# mcp23s17.net
KiCad netlist of a schematic drawn in EAGLE
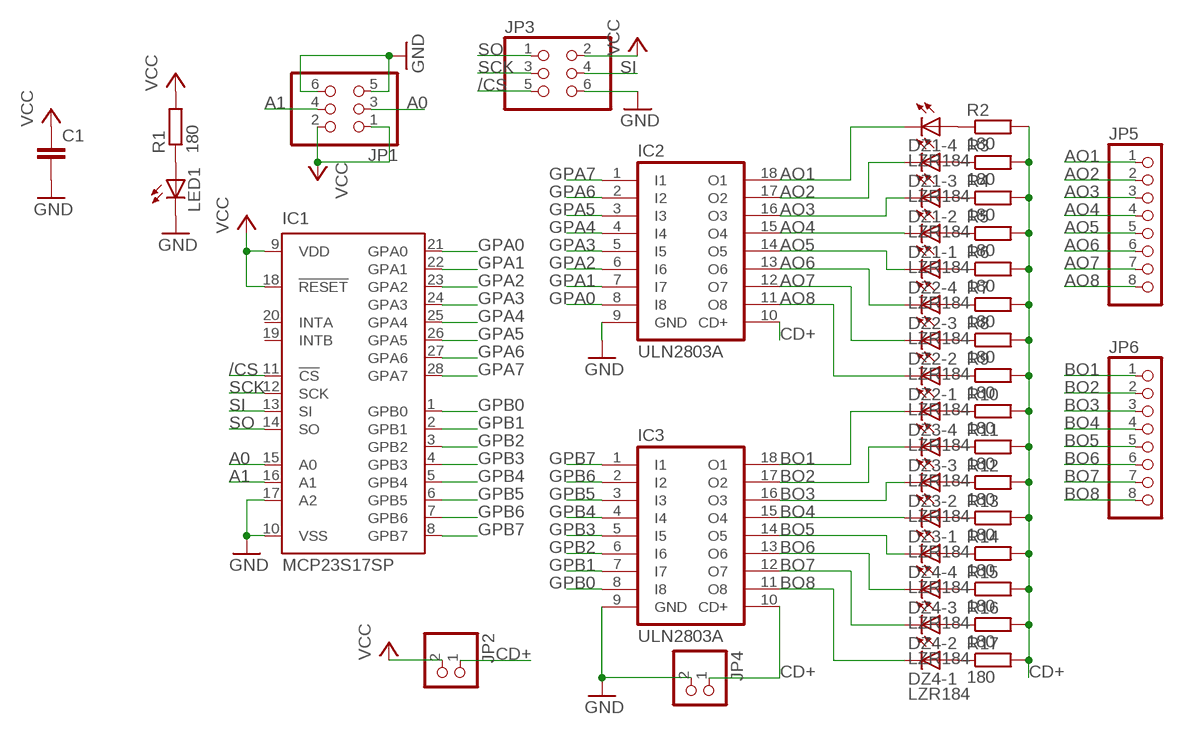
[diagram p0: schematic, sheet 1]

(export (version "E")
  (design (tool "Eeschema 10.0.6"))
  (components
    (comp (ref "C1")
      (value "C-EU050-024X044")
      (footprint "eagle-import:C050-024X044")
      (libsource (lib "eagle-import") (part "C-EU050-024X044"))
    )
    (comp (ref "DZ1")
      (value "LZR184")
      (footprint "eagle-import:LZR184")
      (libsource (lib "eagle-import") (part "LZR184"))
    )
    (comp (ref "DZ2")
      (value "LZR184")
      (footprint "eagle-import:LZR184")
      (libsource (lib "eagle-import") (part "LZR184"))
    )
    (comp (ref "DZ3")
      (value "LZR184")
      (footprint "eagle-import:LZR184")
      (libsource (lib "eagle-import") (part "LZR184"))
    )
    (comp (ref "DZ4")
      (value "LZR184")
      (footprint "eagle-import:LZR184")
      (libsource (lib "eagle-import") (part "LZR184"))
    )
    (comp (ref "IC1")
      (value "MCP23S17SP")
      (footprint "eagle-import:DIL28-3")
      (fields (field (name "MF") "MICROCHIP") (field (name "MPN") "MCP23S17-E/SP"))
      (libsource (lib "eagle-import") (part "MCP23S17SP"))
    )
    (comp (ref "IC2")
      (value "ULN2803A")
      (footprint "eagle-import:DIL18")
      (libsource (lib "eagle-import") (part "ULN2803A"))
    )
    (comp (ref "IC3")
      (value "ULN2803A")
      (footprint "eagle-import:DIL18")
      (libsource (lib "eagle-import") (part "ULN2803A"))
    )
    (comp (ref "JP1")
      (value "PINHD-2X3")
      (footprint "eagle-import:2X03")
      (libsource (lib "eagle-import") (part "PINHD-2X3"))
    )
    (comp (ref "JP2")
      (value "PINHD-1X2")
      (footprint "eagle-import:1X02")
      (libsource (lib "eagle-import") (part "PINHD-1X2"))
    )
    (comp (ref "JP3")
      (value "PINHD-2X3")
      (footprint "eagle-import:2X03")
      (libsource (lib "eagle-import") (part "PINHD-2X3"))
    )
    (comp (ref "JP4")
      (value "PINHD-1X2")
      (footprint "eagle-import:1X02")
      (libsource (lib "eagle-import") (part "PINHD-1X2"))
    )
    (comp (ref "JP5")
      (value "PINHD-1X8")
      (footprint "eagle-import:1X08")
      (libsource (lib "eagle-import") (part "PINHD-1X8"))
    )
    (comp (ref "JP6")
      (value "PINHD-1X8")
      (footprint "eagle-import:1X08")
      (libsource (lib "eagle-import") (part "PINHD-1X8"))
    )
    (comp (ref "LED1")
      (value "LED3MM")
      (footprint "eagle-import:LED3MM")
      (libsource (lib "eagle-import") (part "LED3MM"))
    )
    (comp (ref "R1")
      (value "180")
      (footprint "eagle-import:0204V")
      (libsource (lib "eagle-import") (part "R-EU_0204/2V"))
    )
    (comp (ref "R2")
      (value "180")
      (footprint "eagle-import:0204V")
      (libsource (lib "eagle-import") (part "R-EU_0204/2V"))
    )
    (comp (ref "R3")
      (value "180")
      (footprint "eagle-import:0204V")
      (libsource (lib "eagle-import") (part "R-EU_0204/2V"))
    )
    (comp (ref "R4")
      (value "180")
      (footprint "eagle-import:0204V")
      (libsource (lib "eagle-import") (part "R-EU_0204/2V"))
    )
    (comp (ref "R5")
      (value "180")
      (footprint "eagle-import:0204V")
      (libsource (lib "eagle-import") (part "R-EU_0204/2V"))
    )
    (comp (ref "R6")
      (value "180")
      (footprint "eagle-import:0204V")
      (libsource (lib "eagle-import") (part "R-EU_0204/2V"))
    )
    (comp (ref "R7")
      (value "180")
      (footprint "eagle-import:0204V")
      (libsource (lib "eagle-import") (part "R-EU_0204/2V"))
    )
    (comp (ref "R8")
      (value "180")
      (footprint "eagle-import:0204V")
      (libsource (lib "eagle-import") (part "R-EU_0204/2V"))
    )
    (comp (ref "R9")
      (value "180")
      (footprint "eagle-import:0204V")
      (libsource (lib "eagle-import") (part "R-EU_0204/2V"))
    )
    (comp (ref "R10")
      (value "180")
      (footprint "eagle-import:0204V")
      (libsource (lib "eagle-import") (part "R-EU_0204/2V"))
    )
    (comp (ref "R11")
      (value "180")
      (footprint "eagle-import:0204V")
      (libsource (lib "eagle-import") (part "R-EU_0204/2V"))
    )
    (comp (ref "R12")
      (value "180")
      (footprint "eagle-import:0204V")
      (libsource (lib "eagle-import") (part "R-EU_0204/2V"))
    )
    (comp (ref "R13")
      (value "180")
      (footprint "eagle-import:0204V")
      (libsource (lib "eagle-import") (part "R-EU_0204/2V"))
    )
    (comp (ref "R14")
      (value "180")
      (footprint "eagle-import:0204V")
      (libsource (lib "eagle-import") (part "R-EU_0204/2V"))
    )
    (comp (ref "R15")
      (value "180")
      (footprint "eagle-import:0204V")
      (libsource (lib "eagle-import") (part "R-EU_0204/2V"))
    )
    (comp (ref "R16")
      (value "180")
      (footprint "eagle-import:0204V")
      (libsource (lib "eagle-import") (part "R-EU_0204/2V"))
    )
    (comp (ref "R17")
      (value "180")
      (footprint "eagle-import:0204V")
      (libsource (lib "eagle-import") (part "R-EU_0204/2V"))
    )
  )
  (nets
    (net (code "1") (name "/A0") (class "Default")
      (node (ref "IC1") (pin "15") (pinfunction "A0_15") (pintype "input"))
      (node (ref "JP1") (pin "3") (pinfunction "3_3") (pintype "passive"))
    )
    (net (code "2") (name "/A1") (class "Default")
      (node (ref "IC1") (pin "16") (pinfunction "A1_16") (pintype "input"))
      (node (ref "JP1") (pin "4") (pinfunction "4_4") (pintype "passive"))
    )
    (net (code "3") (name "/AO1") (class "Default")
      (node (ref "DZ1") (pin "K4") (pinfunction "C_K4") (pintype "passive"))
      (node (ref "IC2") (pin "18") (pinfunction "O1_18") (pintype "open_collector"))
      (node (ref "JP5") (pin "1") (pinfunction "1_1") (pintype "passive"))
    )
    (net (code "4") (name "/AO2") (class "Default")
      (node (ref "DZ1") (pin "K3") (pinfunction "C_K3") (pintype "passive"))
      (node (ref "IC2") (pin "17") (pinfunction "O2_17") (pintype "open_collector"))
      (node (ref "JP5") (pin "2") (pinfunction "2_2") (pintype "passive"))
    )
    (net (code "5") (name "/AO3") (class "Default")
      (node (ref "DZ1") (pin "K2") (pinfunction "C_K2") (pintype "passive"))
      (node (ref "IC2") (pin "16") (pinfunction "O3_16") (pintype "open_collector"))
      (node (ref "JP5") (pin "3") (pinfunction "3_3") (pintype "passive"))
    )
    (net (code "6") (name "/AO4") (class "Default")
      (node (ref "DZ1") (pin "K1") (pinfunction "C_K1") (pintype "passive"))
      (node (ref "IC2") (pin "15") (pinfunction "O4_15") (pintype "open_collector"))
      (node (ref "JP5") (pin "4") (pinfunction "4_4") (pintype "passive"))
    )
    (net (code "7") (name "/AO5") (class "Default")
      (node (ref "DZ2") (pin "K4") (pinfunction "C_K4") (pintype "passive"))
      (node (ref "IC2") (pin "14") (pinfunction "O5_14") (pintype "open_collector"))
      (node (ref "JP5") (pin "5") (pinfunction "5_5") (pintype "passive"))
    )
    (net (code "8") (name "/AO6") (class "Default")
      (node (ref "DZ2") (pin "K3") (pinfunction "C_K3") (pintype "passive"))
      (node (ref "IC2") (pin "13") (pinfunction "O6_13") (pintype "open_collector"))
      (node (ref "JP5") (pin "6") (pinfunction "6_6") (pintype "passive"))
    )
    (net (code "9") (name "/AO7") (class "Default")
      (node (ref "DZ2") (pin "K2") (pinfunction "C_K2") (pintype "passive"))
      (node (ref "IC2") (pin "12") (pinfunction "O7_12") (pintype "open_collector"))
      (node (ref "JP5") (pin "7") (pinfunction "7_7") (pintype "passive"))
    )
    (net (code "10") (name "/AO8") (class "Default")
      (node (ref "DZ2") (pin "K1") (pinfunction "C_K1") (pintype "passive"))
      (node (ref "IC2") (pin "11") (pinfunction "O8_11") (pintype "open_collector"))
      (node (ref "JP5") (pin "8") (pinfunction "8_8") (pintype "passive"))
    )
    (net (code "11") (name "/BO1") (class "Default")
      (node (ref "DZ3") (pin "K4") (pinfunction "C_K4") (pintype "passive"))
      (node (ref "IC3") (pin "18") (pinfunction "O1_18") (pintype "open_collector"))
      (node (ref "JP6") (pin "1") (pinfunction "1_1") (pintype "passive"))
    )
    (net (code "12") (name "/BO2") (class "Default")
      (node (ref "DZ3") (pin "K3") (pinfunction "C_K3") (pintype "passive"))
      (node (ref "IC3") (pin "17") (pinfunction "O2_17") (pintype "open_collector"))
      (node (ref "JP6") (pin "2") (pinfunction "2_2") (pintype "passive"))
    )
    (net (code "13") (name "/BO3") (class "Default")
      (node (ref "DZ3") (pin "K2") (pinfunction "C_K2") (pintype "passive"))
      (node (ref "IC3") (pin "16") (pinfunction "O3_16") (pintype "open_collector"))
      (node (ref "JP6") (pin "3") (pinfunction "3_3") (pintype "passive"))
    )
    (net (code "14") (name "/BO4") (class "Default")
      (node (ref "DZ3") (pin "K1") (pinfunction "C_K1") (pintype "passive"))
      (node (ref "IC3") (pin "15") (pinfunction "O4_15") (pintype "open_collector"))
      (node (ref "JP6") (pin "4") (pinfunction "4_4") (pintype "passive"))
    )
    (net (code "15") (name "/BO5") (class "Default")
      (node (ref "DZ4") (pin "K4") (pinfunction "C_K4") (pintype "passive"))
      (node (ref "IC3") (pin "14") (pinfunction "O5_14") (pintype "open_collector"))
      (node (ref "JP6") (pin "5") (pinfunction "5_5") (pintype "passive"))
    )
    (net (code "16") (name "/BO6") (class "Default")
      (node (ref "DZ4") (pin "K3") (pinfunction "C_K3") (pintype "passive"))
      (node (ref "IC3") (pin "13") (pinfunction "O6_13") (pintype "open_collector"))
      (node (ref "JP6") (pin "6") (pinfunction "6_6") (pintype "passive"))
    )
    (net (code "17") (name "/BO7") (class "Default")
      (node (ref "DZ4") (pin "K2") (pinfunction "C_K2") (pintype "passive"))
      (node (ref "IC3") (pin "12") (pinfunction "O7_12") (pintype "open_collector"))
      (node (ref "JP6") (pin "7") (pinfunction "7_7") (pintype "passive"))
    )
    (net (code "18") (name "/BO8") (class "Default")
      (node (ref "DZ4") (pin "K1") (pinfunction "C_K1") (pintype "passive"))
      (node (ref "IC3") (pin "11") (pinfunction "O8_11") (pintype "open_collector"))
      (node (ref "JP6") (pin "8") (pinfunction "8_8") (pintype "passive"))
    )
    (net (code "19") (name "/CD+") (class "Default")
      (node (ref "IC2") (pin "10") (pinfunction "CD+_10") (pintype "passive"))
      (node (ref "IC3") (pin "10") (pinfunction "CD+_10") (pintype "passive"))
      (node (ref "JP2") (pin "1") (pinfunction "1_1") (pintype "passive"))
      (node (ref "JP4") (pin "1") (pinfunction "1_1") (pintype "passive"))
      (node (ref "R10") (pin "2") (pinfunction "2_2") (pintype "passive"))
      (node (ref "R11") (pin "2") (pinfunction "2_2") (pintype "passive"))
      (node (ref "R12") (pin "2") (pinfunction "2_2") (pintype "passive"))
      (node (ref "R13") (pin "2") (pinfunction "2_2") (pintype "passive"))
      (node (ref "R14") (pin "2") (pinfunction "2_2") (pintype "passive"))
      (node (ref "R15") (pin "2") (pinfunction "2_2") (pintype "passive"))
      (node (ref "R16") (pin "2") (pinfunction "2_2") (pintype "passive"))
      (node (ref "R17") (pin "2") (pinfunction "2_2") (pintype "passive"))
      (node (ref "R2") (pin "2") (pinfunction "2_2") (pintype "passive"))
      (node (ref "R3") (pin "2") (pinfunction "2_2") (pintype "passive"))
      (node (ref "R4") (pin "2") (pinfunction "2_2") (pintype "passive"))
      (node (ref "R5") (pin "2") (pinfunction "2_2") (pintype "passive"))
      (node (ref "R6") (pin "2") (pinfunction "2_2") (pintype "passive"))
      (node (ref "R7") (pin "2") (pinfunction "2_2") (pintype "passive"))
      (node (ref "R8") (pin "2") (pinfunction "2_2") (pintype "passive"))
      (node (ref "R9") (pin "2") (pinfunction "2_2") (pintype "passive"))
    )
    (net (code "20") (name "/GPA0") (class "Default")
      (node (ref "IC1") (pin "21") (pinfunction "GPA0_21") (pintype "bidirectional"))
      (node (ref "IC2") (pin "8") (pinfunction "I8_8") (pintype "input"))
    )
    (net (code "21") (name "/GPA1") (class "Default")
      (node (ref "IC1") (pin "22") (pinfunction "GPA1_22") (pintype "bidirectional"))
      (node (ref "IC2") (pin "7") (pinfunction "I7_7") (pintype "input"))
    )
    (net (code "22") (name "/GPA2") (class "Default")
      (node (ref "IC1") (pin "23") (pinfunction "GPA2_23") (pintype "bidirectional"))
      (node (ref "IC2") (pin "6") (pinfunction "I6_6") (pintype "input"))
    )
    (net (code "23") (name "/GPA3") (class "Default")
      (node (ref "IC1") (pin "24") (pinfunction "GPA3_24") (pintype "bidirectional"))
      (node (ref "IC2") (pin "5") (pinfunction "I5_5") (pintype "input"))
    )
    (net (code "24") (name "/GPA4") (class "Default")
      (node (ref "IC1") (pin "25") (pinfunction "GPA4_25") (pintype "bidirectional"))
      (node (ref "IC2") (pin "4") (pinfunction "I4_4") (pintype "input"))
    )
    (net (code "25") (name "/GPA5") (class "Default")
      (node (ref "IC1") (pin "26") (pinfunction "GPA5_26") (pintype "bidirectional"))
      (node (ref "IC2") (pin "3") (pinfunction "I3_3") (pintype "input"))
    )
    (net (code "26") (name "/GPA6") (class "Default")
      (node (ref "IC1") (pin "27") (pinfunction "GPA6_27") (pintype "bidirectional"))
      (node (ref "IC2") (pin "2") (pinfunction "I2_2") (pintype "input"))
    )
    (net (code "27") (name "/GPA7") (class "Default")
      (node (ref "IC1") (pin "28") (pinfunction "GPA7_28") (pintype "bidirectional"))
      (node (ref "IC2") (pin "1") (pinfunction "I1_1") (pintype "input"))
    )
    (net (code "28") (name "/GPB0") (class "Default")
      (node (ref "IC1") (pin "1") (pinfunction "GPB0_1") (pintype "bidirectional"))
      (node (ref "IC3") (pin "8") (pinfunction "I8_8") (pintype "input"))
    )
    (net (code "29") (name "/GPB1") (class "Default")
      (node (ref "IC1") (pin "2") (pinfunction "GPB1_2") (pintype "bidirectional"))
      (node (ref "IC3") (pin "7") (pinfunction "I7_7") (pintype "input"))
    )
    (net (code "30") (name "/GPB2") (class "Default")
      (node (ref "IC1") (pin "3") (pinfunction "GPB2_3") (pintype "bidirectional"))
      (node (ref "IC3") (pin "6") (pinfunction "I6_6") (pintype "input"))
    )
    (net (code "31") (name "/GPB3") (class "Default")
      (node (ref "IC1") (pin "4") (pinfunction "GPB3_4") (pintype "bidirectional"))
      (node (ref "IC3") (pin "5") (pinfunction "I5_5") (pintype "input"))
    )
    (net (code "32") (name "/GPB4") (class "Default")
      (node (ref "IC1") (pin "5") (pinfunction "GPB4_5") (pintype "bidirectional"))
      (node (ref "IC3") (pin "4") (pinfunction "I4_4") (pintype "input"))
    )
    (net (code "33") (name "/GPB5") (class "Default")
      (node (ref "IC1") (pin "6") (pinfunction "GPB5_6") (pintype "bidirectional"))
      (node (ref "IC3") (pin "3") (pinfunction "I3_3") (pintype "input"))
    )
    (net (code "34") (name "/GPB6") (class "Default")
      (node (ref "IC1") (pin "7") (pinfunction "GPB6_7") (pintype "bidirectional"))
      (node (ref "IC3") (pin "2") (pinfunction "I2_2") (pintype "input"))
    )
    (net (code "35") (name "/GPB7") (class "Default")
      (node (ref "IC1") (pin "8") (pinfunction "GPB7_8") (pintype "bidirectional"))
      (node (ref "IC3") (pin "1") (pinfunction "I1_1") (pintype "input"))
    )
    (net (code "36") (name "/SCK") (class "Default")
      (node (ref "IC1") (pin "12") (pinfunction "SCK_12") (pintype "input"))
      (node (ref "JP3") (pin "3") (pinfunction "3_3") (pintype "passive"))
    )
    (net (code "37") (name "/SI") (class "Default")
      (node (ref "IC1") (pin "13") (pinfunction "SI_13") (pintype "input"))
      (node (ref "JP3") (pin "4") (pinfunction "4_4") (pintype "passive"))
    )
    (net (code "38") (name "/SO") (class "Default")
      (node (ref "IC1") (pin "14") (pinfunction "SO_14") (pintype "output"))
      (node (ref "JP3") (pin "1") (pinfunction "1_1") (pintype "passive"))
    )
    (net (code "39") (name "/{slash}CS") (class "Default")
      (node (ref "IC1") (pin "11") (pinfunction "~{CS}_11") (pintype "input"))
      (node (ref "JP3") (pin "5") (pinfunction "5_5") (pintype "passive"))
    )
    (net (code "40") (name "GND") (class "Default")
      (node (ref "C1") (pin "2") (pinfunction "2_2") (pintype "passive"))
      (node (ref "IC1") (pin "10") (pinfunction "VSS_10") (pintype "power_in"))
      (node (ref "IC1") (pin "17") (pinfunction "A2_17") (pintype "input"))
      (node (ref "IC2") (pin "9") (pinfunction "GND_9") (pintype "power_in"))
      (node (ref "IC3") (pin "9") (pinfunction "GND_9") (pintype "power_in"))
      (node (ref "JP1") (pin "5") (pinfunction "5_5") (pintype "passive"))
      (node (ref "JP1") (pin "6") (pinfunction "6_6") (pintype "passive"))
      (node (ref "JP3") (pin "6") (pinfunction "6_6") (pintype "passive"))
      (node (ref "JP4") (pin "2") (pinfunction "2_2") (pintype "passive"))
      (node (ref "LED1") (pin "K") (pinfunction "C_K") (pintype "passive"))
    )
    (net (code "41") (name "Net-(DZ1A-A)") (class "Default")
      (node (ref "DZ1") (pin "A1") (pinfunction "A_A1") (pintype "passive"))
      (node (ref "R5") (pin "1") (pinfunction "1_1") (pintype "passive"))
    )
    (net (code "42") (name "Net-(DZ1B-A)") (class "Default")
      (node (ref "DZ1") (pin "A2") (pinfunction "A_A2") (pintype "passive"))
      (node (ref "R4") (pin "1") (pinfunction "1_1") (pintype "passive"))
    )
    (net (code "43") (name "Net-(DZ1C-A)") (class "Default")
      (node (ref "DZ1") (pin "A3") (pinfunction "A_A3") (pintype "passive"))
      (node (ref "R3") (pin "1") (pinfunction "1_1") (pintype "passive"))
    )
    (net (code "44") (name "Net-(DZ1D-A)") (class "Default")
      (node (ref "DZ1") (pin "A4") (pinfunction "A_A4") (pintype "passive"))
      (node (ref "R2") (pin "1") (pinfunction "1_1") (pintype "passive"))
    )
    (net (code "45") (name "Net-(DZ2A-A)") (class "Default")
      (node (ref "DZ2") (pin "A1") (pinfunction "A_A1") (pintype "passive"))
      (node (ref "R9") (pin "1") (pinfunction "1_1") (pintype "passive"))
    )
    (net (code "46") (name "Net-(DZ2B-A)") (class "Default")
      (node (ref "DZ2") (pin "A2") (pinfunction "A_A2") (pintype "passive"))
      (node (ref "R8") (pin "1") (pinfunction "1_1") (pintype "passive"))
    )
    (net (code "47") (name "Net-(DZ2C-A)") (class "Default")
      (node (ref "DZ2") (pin "A3") (pinfunction "A_A3") (pintype "passive"))
      (node (ref "R7") (pin "1") (pinfunction "1_1") (pintype "passive"))
    )
    (net (code "48") (name "Net-(DZ2D-A)") (class "Default")
      (node (ref "DZ2") (pin "A4") (pinfunction "A_A4") (pintype "passive"))
      (node (ref "R6") (pin "1") (pinfunction "1_1") (pintype "passive"))
    )
    (net (code "49") (name "Net-(DZ3A-A)") (class "Default")
      (node (ref "DZ3") (pin "A1") (pinfunction "A_A1") (pintype "passive"))
      (node (ref "R13") (pin "1") (pinfunction "1_1") (pintype "passive"))
    )
    (net (code "50") (name "Net-(DZ3B-A)") (class "Default")
      (node (ref "DZ3") (pin "A2") (pinfunction "A_A2") (pintype "passive"))
      (node (ref "R12") (pin "1") (pinfunction "1_1") (pintype "passive"))
    )
    (net (code "51") (name "Net-(DZ3C-A)") (class "Default")
      (node (ref "DZ3") (pin "A3") (pinfunction "A_A3") (pintype "passive"))
      (node (ref "R11") (pin "1") (pinfunction "1_1") (pintype "passive"))
    )
    (net (code "52") (name "Net-(DZ3D-A)") (class "Default")
      (node (ref "DZ3") (pin "A4") (pinfunction "A_A4") (pintype "passive"))
      (node (ref "R10") (pin "1") (pinfunction "1_1") (pintype "passive"))
    )
    (net (code "53") (name "Net-(DZ4A-A)") (class "Default")
      (node (ref "DZ4") (pin "A1") (pinfunction "A_A1") (pintype "passive"))
      (node (ref "R17") (pin "1") (pinfunction "1_1") (pintype "passive"))
    )
    (net (code "54") (name "Net-(DZ4B-A)") (class "Default")
      (node (ref "DZ4") (pin "A2") (pinfunction "A_A2") (pintype "passive"))
      (node (ref "R16") (pin "1") (pinfunction "1_1") (pintype "passive"))
    )
    (net (code "55") (name "Net-(DZ4C-A)") (class "Default")
      (node (ref "DZ4") (pin "A3") (pinfunction "A_A3") (pintype "passive"))
      (node (ref "R15") (pin "1") (pinfunction "1_1") (pintype "passive"))
    )
    (net (code "56") (name "Net-(DZ4D-A)") (class "Default")
      (node (ref "DZ4") (pin "A4") (pinfunction "A_A4") (pintype "passive"))
      (node (ref "R14") (pin "1") (pinfunction "1_1") (pintype "passive"))
    )
    (net (code "57") (name "Net-(LED1-PadA)") (class "Default")
      (node (ref "LED1") (pin "A") (pinfunction "A_A") (pintype "passive"))
      (node (ref "R1") (pin "1") (pinfunction "1_1") (pintype "passive"))
    )
    (net (code "58") (name "VCC") (class "Default")
      (node (ref "C1") (pin "1") (pinfunction "1_1") (pintype "passive"))
      (node (ref "IC1") (pin "18") (pinfunction "~{RESET}_18") (pintype "input"))
      (node (ref "IC1") (pin "9") (pinfunction "VDD_9") (pintype "power_in"))
      (node (ref "JP1") (pin "1") (pinfunction "1_1") (pintype "passive"))
      (node (ref "JP1") (pin "2") (pinfunction "2_2") (pintype "passive"))
      (node (ref "JP2") (pin "2") (pinfunction "2_2") (pintype "passive"))
      (node (ref "JP3") (pin "2") (pinfunction "2_2") (pintype "passive"))
      (node (ref "R1") (pin "2") (pinfunction "2_2") (pintype "passive"))
    )
    (net (code "59") (name "unconnected-(IC1-INTA-Pad20)") (class "Default")
      (node (ref "IC1") (pin "20") (pinfunction "INTA_20") (pintype "output"))
    )
    (net (code "60") (name "unconnected-(IC1-INTB-Pad19)") (class "Default")
      (node (ref "IC1") (pin "19") (pinfunction "INTB_19") (pintype "output"))
    )
  )
)
